# BaseDimmerBoard.net
KiCad netlist of a schematic drawn in Altium Designer
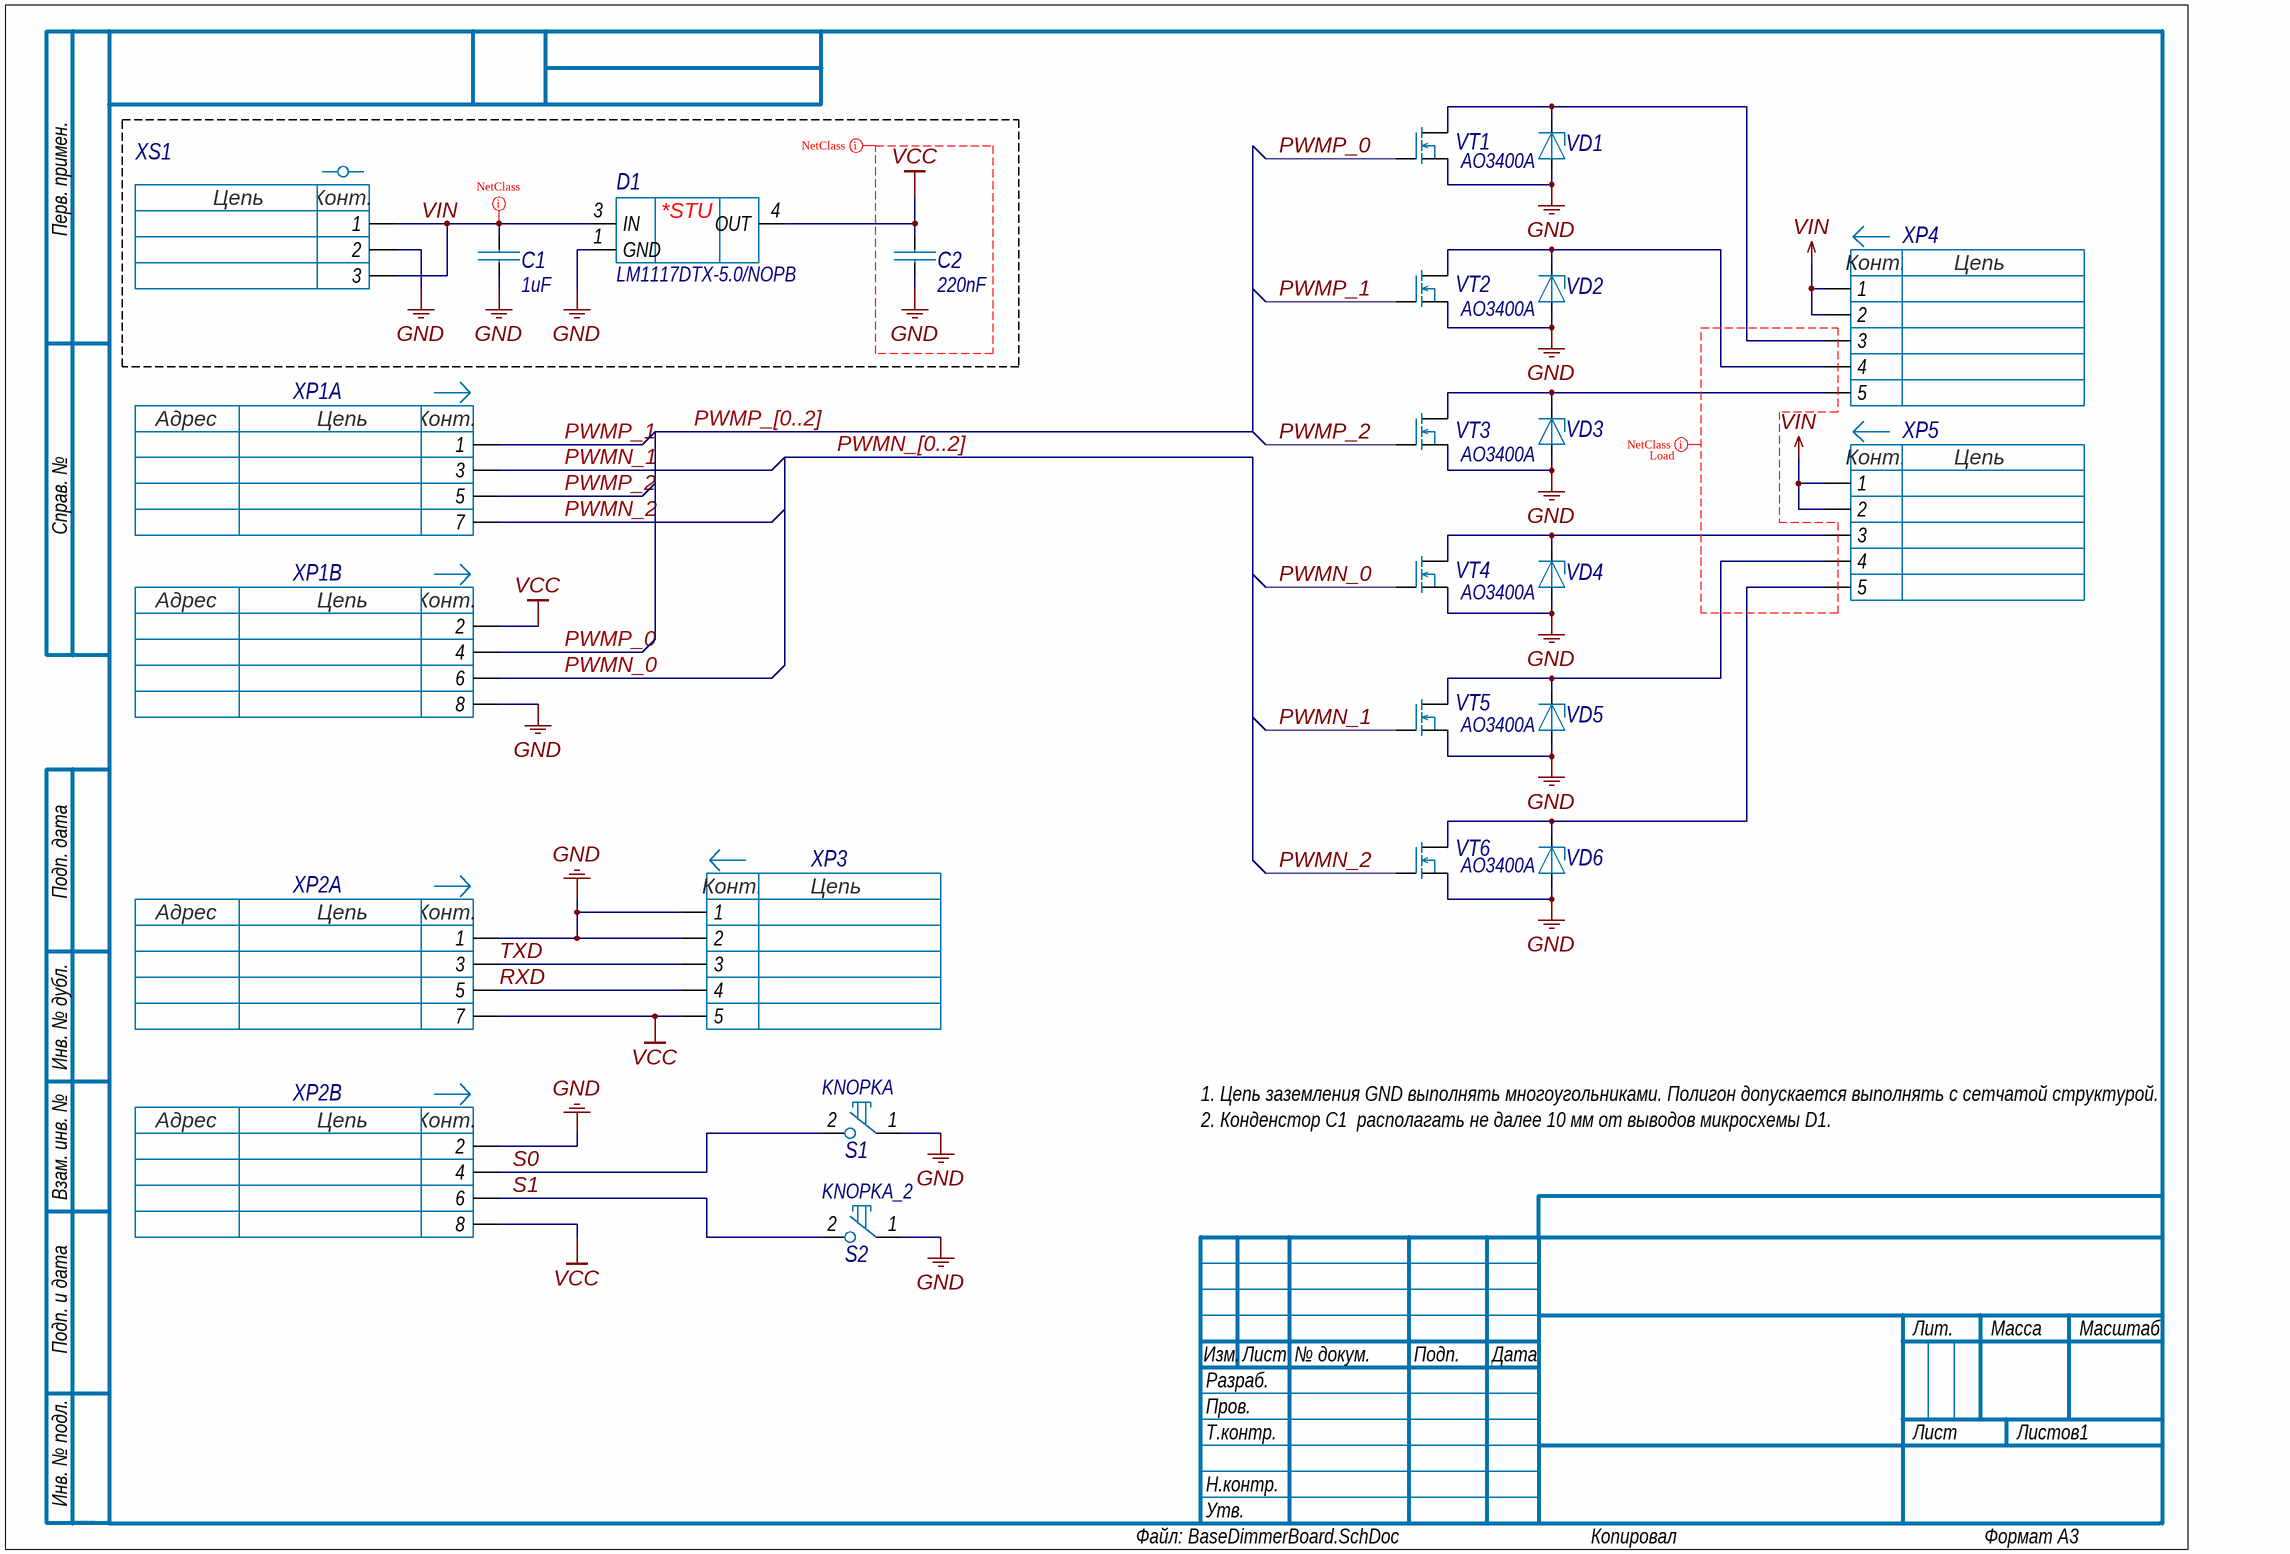
[diagram p0: BaseDimmerBoard.SchDoc]

(export (version "E")
  (design (tool "Eeschema 10.0.6"))
  (components
    (comp (ref "C1")
      (value "1uF")
      (footprint "Dimmer:CAPC1825(4564)220_N")
      (description "Керамический чип-конденсатор")
      (fields (field (name "TOLERANCE") "10%") (field (name "MANUFACTURER PART NUMBER") "VJ1825Y105KXXAT"))
      (libsource (lib "Dimmer") (part "VJ1825Y105KXXAT"))
    )
    (comp (ref "C2")
      (value "220nF")
      (footprint "Dimmer:CAPC0805(2012)100_N")
      (description "Керамический чип-конденсатор")
      (fields (field (name "TOLERANCE") "20%") (field (name "MANUFACTURER PART NUMBER") "LLM215R70J224MA11L"))
      (libsource (lib "Dimmer") (part "LLM215R70J224MA11L"))
    )
    (comp (ref "D1")
      (value "LM1117DTX-5.0/NOPB")
      (footprint "Dimmer:NDP0003B_L")
      (description "LDO Regulator Pos 5V 0.8A 3-Pin(2+Tab) TO-252 T/R")
      (fields (field (name "MANUFACTURER") "TI National Semiconductor"))
      (libsource (lib "Dimmer") (part "LM1117DTX-5.0/NOPB"))
    )
    (comp (ref "S1")
      (value "KNOPKA")
      (footprint "Dimmer:ELASTO_5.08MM")
      (fields (field (name "MANUFACTURER PART NUMBER") "Сенсор"))
      (libsource (lib "Dimmer") (part "KNOPKA"))
    )
    (comp (ref "S2")
      (value "KNOPKA_2")
      (footprint "Dimmer:DOME_SQ04200N")
      (fields (field (name "MANUFACTURER PART NUMBER") "Сенсор"))
      (libsource (lib "Dimmer") (part "KNOPKA_2"))
    )
    (comp (ref "VD1")
      (value "P6SMB27AT3G")
      (footprint "Dimmer:ONSC-SMB-2-403A-03_J_V")
      (description "TVS DIODE 23.1V 37.5V SMB")
      (fields (field (name "MANUFACTURER") "ON Semiconductor"))
      (libsource (lib "Dimmer") (part "P6SMB27AT3G"))
    )
    (comp (ref "VD2")
      (value "P6SMB27AT3G")
      (footprint "Dimmer:ONSC-SMB-2-403A-03_J_V")
      (description "TVS DIODE 23.1V 37.5V SMB")
      (fields (field (name "MANUFACTURER") "ON Semiconductor"))
      (libsource (lib "Dimmer") (part "P6SMB27AT3G"))
    )
    (comp (ref "VD3")
      (value "P6SMB27AT3G")
      (footprint "Dimmer:ONSC-SMB-2-403A-03_J_V")
      (description "TVS DIODE 23.1V 37.5V SMB")
      (fields (field (name "MANUFACTURER") "ON Semiconductor"))
      (libsource (lib "Dimmer") (part "P6SMB27AT3G"))
    )
    (comp (ref "VD4")
      (value "P6SMB27AT3G")
      (footprint "Dimmer:ONSC-SMB-2-403A-03_J_V")
      (description "TVS DIODE 23.1V 37.5V SMB")
      (fields (field (name "MANUFACTURER") "ON Semiconductor"))
      (libsource (lib "Dimmer") (part "P6SMB27AT3G"))
    )
    (comp (ref "VD5")
      (value "P6SMB27AT3G")
      (footprint "Dimmer:ONSC-SMB-2-403A-03_J_V")
      (description "TVS DIODE 23.1V 37.5V SMB")
      (fields (field (name "MANUFACTURER") "ON Semiconductor"))
      (libsource (lib "Dimmer") (part "P6SMB27AT3G"))
    )
    (comp (ref "VD6")
      (value "P6SMB27AT3G")
      (footprint "Dimmer:ONSC-SMB-2-403A-03_J_V")
      (description "TVS DIODE 23.1V 37.5V SMB")
      (fields (field (name "MANUFACTURER") "ON Semiconductor"))
      (libsource (lib "Dimmer") (part "P6SMB27AT3G"))
    )
    (comp (ref "VT1")
      (value "AO3400A")
      (footprint "Dimmer:AO-SOT23-3_V")
      (description "MOSFET N-CH 30V 5.7A SOT23")
      (fields (field (name "MANUFACTURER") "Alpha & Omega Semiconductor"))
      (libsource (lib "Dimmer") (part "AO3400A"))
    )
    (comp (ref "VT2")
      (value "AO3400A")
      (footprint "Dimmer:AO-SOT23-3_V")
      (description "MOSFET N-CH 30V 5.7A SOT23")
      (fields (field (name "MANUFACTURER") "Alpha & Omega Semiconductor"))
      (libsource (lib "Dimmer") (part "AO3400A"))
    )
    (comp (ref "VT3")
      (value "AO3400A")
      (footprint "Dimmer:AO-SOT23-3_V")
      (description "MOSFET N-CH 30V 5.7A SOT23")
      (fields (field (name "MANUFACTURER") "Alpha & Omega Semiconductor"))
      (libsource (lib "Dimmer") (part "AO3400A"))
    )
    (comp (ref "VT4")
      (value "AO3400A")
      (footprint "Dimmer:AO-SOT23-3_V")
      (description "MOSFET N-CH 30V 5.7A SOT23")
      (fields (field (name "MANUFACTURER") "Alpha & Omega Semiconductor"))
      (libsource (lib "Dimmer") (part "AO3400A"))
    )
    (comp (ref "VT5")
      (value "AO3400A")
      (footprint "Dimmer:AO-SOT23-3_V")
      (description "MOSFET N-CH 30V 5.7A SOT23")
      (fields (field (name "MANUFACTURER") "Alpha & Omega Semiconductor"))
      (libsource (lib "Dimmer") (part "AO3400A"))
    )
    (comp (ref "VT6")
      (value "AO3400A")
      (footprint "Dimmer:AO-SOT23-3_V")
      (description "MOSFET N-CH 30V 5.7A SOT23")
      (fields (field (name "MANUFACTURER") "Alpha & Omega Semiconductor"))
      (libsource (lib "Dimmer") (part "AO3400A"))
    )
    (comp (ref "XP1")
      (value "TSM-104-04-T-DV")
      (footprint "Dimmer:TSM-104-04-T-DV")
      (fields
        (field (name "MANUFACTURER PART NUMBER") "TSM-104-04-T-DV.1")
        (field (name "MANUFACTURER") "Samtec")
      )
      (libsource (lib "Dimmer") (part "TSM-104-04-T-DV"))
    )
    (comp (ref "XP2")
      (value "TSM-104-04-T-DV")
      (footprint "Dimmer:TSM-104-04-T-DV")
      (fields
        (field (name "MANUFACTURER PART NUMBER") "TSM-104-04-T-DV.1")
        (field (name "MANUFACTURER") "Samtec")
      )
      (libsource (lib "Dimmer") (part "TSM-104-04-T-DV"))
    )
    (comp (ref "XP3")
      (value "TSW-105-05-T-S")
      (footprint "Dimmer:SMTC-TSW-105-05-X-S")
      (description "TSW - Samtec 2.54mm Pin Header 13.46mm Overall Pin Length 5.08mm Tail (08)")
      (fields (field (name "MANUFACTURER") "Samtec"))
      (libsource (lib "Dimmer") (part "TSW-105-05-T-S"))
    )
    (comp (ref "XP4")
      (value "TSW-105-05-T-S")
      (footprint "Dimmer:SMTC-TSW-105-05-X-S")
      (description "TSW - Samtec 2.54mm Pin Header 13.46mm Overall Pin Length 5.08mm Tail (08)")
      (fields (field (name "MANUFACTURER") "Samtec"))
      (libsource (lib "Dimmer") (part "TSW-105-05-T-S"))
    )
    (comp (ref "XP5")
      (value "TSW-105-05-T-S")
      (footprint "Dimmer:SMTC-TSW-105-05-X-S")
      (description "TSW - Samtec 2.54mm Pin Header 13.46mm Overall Pin Length 5.08mm Tail (08)")
      (fields (field (name "MANUFACTURER") "Samtec"))
      (libsource (lib "Dimmer") (part "TSW-105-05-T-S"))
    )
    (comp (ref "XS1")
      (value "691213710003")
      (footprint "Dimmer:ETB15-3")
      (description "TERM BLK 5MM HORZ ENTRY MOD 3P")
      (fields (field (name "VOLTAGE") "300V") (field (name "MANUFACTURER") "Wurht Electronics"))
      (libsource (lib "Dimmer") (part "691213710003"))
    )
  )
  (nets
    (net (code "1") (name "/PWMN_0") (class "Default")
      (node (ref "VT4") (pin "G") (pinfunction "G_G") (pintype "passive"))
      (node (ref "XP1") (pin "6") (pinfunction "6_6") (pintype "passive"))
    )
    (net (code "2") (name "/PWMN_1") (class "Default")
      (node (ref "VT5") (pin "G") (pinfunction "G_G") (pintype "passive"))
      (node (ref "XP1") (pin "3") (pinfunction "3_3") (pintype "passive"))
    )
    (net (code "3") (name "/PWMN_2") (class "Default")
      (node (ref "VT6") (pin "G") (pinfunction "G_G") (pintype "passive"))
      (node (ref "XP1") (pin "7") (pinfunction "7_7") (pintype "passive"))
    )
    (net (code "5") (name "/PWMP_0") (class "Default")
      (node (ref "VT1") (pin "G") (pinfunction "G_G") (pintype "passive"))
      (node (ref "XP1") (pin "4") (pinfunction "4_4") (pintype "passive"))
    )
    (net (code "6") (name "/PWMP_1") (class "Default")
      (node (ref "VT2") (pin "G") (pinfunction "G_G") (pintype "passive"))
      (node (ref "XP1") (pin "1") (pinfunction "1_1") (pintype "passive"))
    )
    (net (code "7") (name "/PWMP_2") (class "Default")
      (node (ref "VT3") (pin "G") (pinfunction "G_G") (pintype "passive"))
      (node (ref "XP1") (pin "5") (pinfunction "5_5") (pintype "passive"))
    )
    (net (code "9") (name "/RXD") (class "Default")
      (node (ref "XP2") (pin "5") (pinfunction "5_5") (pintype "passive"))
      (node (ref "XP3") (pin "4") (pinfunction "4_4") (pintype "passive"))
    )
    (net (code "10") (name "/S0") (class "Default")
      (node (ref "S1") (pin "2") (pinfunction "2_2") (pintype "passive"))
      (node (ref "XP2") (pin "4") (pinfunction "4_4") (pintype "passive"))
    )
    (net (code "11") (name "/S1") (class "Default")
      (node (ref "S2") (pin "2") (pinfunction "2_2") (pintype "passive"))
      (node (ref "XP2") (pin "6") (pinfunction "6_6") (pintype "passive"))
    )
    (net (code "12") (name "/TXD") (class "Default")
      (node (ref "XP2") (pin "3") (pinfunction "3_3") (pintype "passive"))
      (node (ref "XP3") (pin "3") (pinfunction "3_3") (pintype "passive"))
    )
    (net (code "13") (name "GND") (class "Default")
      (node (ref "C1") (pin "2") (pinfunction "2_2") (pintype "passive"))
      (node (ref "C2") (pin "1") (pinfunction "1_1") (pintype "passive"))
      (node (ref "D1") (pin "1") (pinfunction "GND_1") (pintype "power_in"))
      (node (ref "S1") (pin "1") (pinfunction "1_1") (pintype "passive"))
      (node (ref "S2") (pin "1") (pinfunction "1_1") (pintype "passive"))
      (node (ref "VD1") (pin "2") (pinfunction "2_2") (pintype "passive"))
      (node (ref "VD2") (pin "2") (pinfunction "2_2") (pintype "passive"))
      (node (ref "VD3") (pin "2") (pinfunction "2_2") (pintype "passive"))
      (node (ref "VD4") (pin "2") (pinfunction "2_2") (pintype "passive"))
      (node (ref "VD5") (pin "2") (pinfunction "2_2") (pintype "passive"))
      (node (ref "VD6") (pin "2") (pinfunction "2_2") (pintype "passive"))
      (node (ref "VT1") (pin "S") (pinfunction "S_S") (pintype "passive"))
      (node (ref "VT2") (pin "S") (pinfunction "S_S") (pintype "passive"))
      (node (ref "VT3") (pin "S") (pinfunction "S_S") (pintype "passive"))
      (node (ref "VT4") (pin "S") (pinfunction "S_S") (pintype "passive"))
      (node (ref "VT5") (pin "S") (pinfunction "S_S") (pintype "passive"))
      (node (ref "VT6") (pin "S") (pinfunction "S_S") (pintype "passive"))
      (node (ref "XP1") (pin "8") (pinfunction "8_8") (pintype "passive"))
      (node (ref "XP2") (pin "1") (pinfunction "1_1") (pintype "passive"))
      (node (ref "XP2") (pin "2") (pinfunction "2_2") (pintype "passive"))
      (node (ref "XP3") (pin "1") (pinfunction "1_1") (pintype "passive"))
      (node (ref "XP3") (pin "2") (pinfunction "2_2") (pintype "passive"))
      (node (ref "XS1") (pin "2") (pinfunction "2_2") (pintype "passive"))
    )
    (net (code "14") (name "Net-(VD1-Pad1)") (class "Default")
      (node (ref "VD1") (pin "1") (pinfunction "1_1") (pintype "passive"))
      (node (ref "VT1") (pin "D") (pinfunction "D_D") (pintype "passive"))
      (node (ref "XP4") (pin "3") (pinfunction "3_3") (pintype "passive"))
    )
    (net (code "15") (name "Net-(VD2-Pad1)") (class "Default")
      (node (ref "VD2") (pin "1") (pinfunction "1_1") (pintype "passive"))
      (node (ref "VT2") (pin "D") (pinfunction "D_D") (pintype "passive"))
      (node (ref "XP4") (pin "4") (pinfunction "4_4") (pintype "passive"))
    )
    (net (code "16") (name "Net-(VD3-Pad1)") (class "Default")
      (node (ref "VD3") (pin "1") (pinfunction "1_1") (pintype "passive"))
      (node (ref "VT3") (pin "D") (pinfunction "D_D") (pintype "passive"))
      (node (ref "XP4") (pin "5") (pinfunction "5_5") (pintype "passive"))
    )
    (net (code "17") (name "Net-(VD4-Pad1)") (class "Default")
      (node (ref "VD4") (pin "1") (pinfunction "1_1") (pintype "passive"))
      (node (ref "VT4") (pin "D") (pinfunction "D_D") (pintype "passive"))
      (node (ref "XP5") (pin "3") (pinfunction "3_3") (pintype "passive"))
    )
    (net (code "18") (name "Net-(VD5-Pad1)") (class "Default")
      (node (ref "VD5") (pin "1") (pinfunction "1_1") (pintype "passive"))
      (node (ref "VT5") (pin "D") (pinfunction "D_D") (pintype "passive"))
      (node (ref "XP5") (pin "4") (pinfunction "4_4") (pintype "passive"))
    )
    (net (code "19") (name "Net-(VD6-Pad1)") (class "Default")
      (node (ref "VD6") (pin "1") (pinfunction "1_1") (pintype "passive"))
      (node (ref "VT6") (pin "D") (pinfunction "D_D") (pintype "passive"))
      (node (ref "XP5") (pin "5") (pinfunction "5_5") (pintype "passive"))
    )
    (net (code "20") (name "VCC") (class "Default")
      (node (ref "C2") (pin "2") (pinfunction "2_2") (pintype "passive"))
      (node (ref "D1") (pin "4") (pinfunction "OUT_4") (pintype "power_in"))
      (node (ref "XP1") (pin "2") (pinfunction "2_2") (pintype "passive"))
      (node (ref "XP2") (pin "7") (pinfunction "7_7") (pintype "passive"))
      (node (ref "XP2") (pin "8") (pinfunction "8_8") (pintype "passive"))
      (node (ref "XP3") (pin "5") (pinfunction "5_5") (pintype "passive"))
    )
    (net (code "21") (name "VIN") (class "Default")
      (node (ref "C1") (pin "1") (pinfunction "1_1") (pintype "passive"))
      (node (ref "D1") (pin "3") (pinfunction "IN_3") (pintype "power_in"))
      (node (ref "XP4") (pin "1") (pinfunction "1_1") (pintype "passive"))
      (node (ref "XP4") (pin "2") (pinfunction "2_2") (pintype "passive"))
      (node (ref "XP5") (pin "1") (pinfunction "1_1") (pintype "passive"))
      (node (ref "XP5") (pin "2") (pinfunction "2_2") (pintype "passive"))
      (node (ref "XS1") (pin "1") (pinfunction "1_1") (pintype "passive"))
      (node (ref "XS1") (pin "3") (pinfunction "3_3") (pintype "passive"))
    )
  )
)
